# Button.net
KiCad netlist of a schematic drawn in Altium Designer
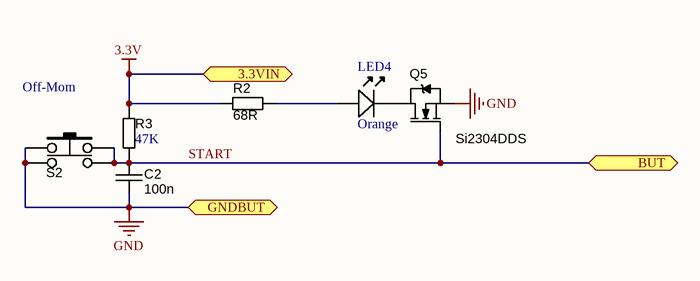
[diagram p0: Button.SchDoc]

(export (version "E")
  (design (tool "Eeschema 10.0.6"))
  (components
    (comp (ref "C2")
      (value "100n")
      (footprint "CAPC1608X90N")
      (description "Capacitor SMD Cer 100nF 10% 50V X7R 0603")
      (fields
        (field (name "TOLERANCE") "±10%")
        (field (name "MANUFACTURER") "Murata Electronics North America")
      )
      (libsource (lib "PBL - Capacitors") (part "CAPC_100n_0603_X7R_50V_10%"))
    )
    (comp (ref "LED4")
      (value "LO L296-Q2S1-24-Z")
      (footprint "LED-0603-AMBER")
      (description "LED ORANGE DIFFUSED 0603 SMD")
      (fields (field (name "COLOR") "Orange") (field (name "MANUFACTURER") "OSRAM Opto Semiconductors Inc."))
      (libsource (lib "PBL - Light Sources") (part "LED_0603_Orange"))
    )
    (comp (ref "Q5")
      (value "Si2304DDS")
      (footprint "SOT23-3")
      (description "MOSFET SMD N-CH 30V 3.6A 1.7W SOT23-3")
      (libsource (lib "PBL - Transistors") (part "MOSFET_Si2304DDS"))
    )
    (comp (ref "R2")
      (value "68R")
      (footprint "RESC1608X55N")
      (description "Resistor SMD chip 68 Ohm 0.1W 5% 0603")
      (fields (field (name "TOLERANCE") "±5%") (field (name "Comment") "Thick Film"))
      (libsource (lib "PBL - Resistors") (part "RES_68R_0603_5%"))
    )
    (comp (ref "R3")
      (value "47K")
      (footprint "RESC1608X55N")
      (description "Resistor SMD chip 47k Ohm 0.1W 1% 0603")
      (fields (field (name "TOLERANCE") "±1%") (field (name "Comment") "Thick Film"))
      (libsource (lib "PBL - Resistors") (part "RES_47K_0603_1%"))
    )
    (comp (ref "S2")
      (value "SW_NO_MOM_PVA1 OA H1 1.2N V2")
      (footprint "SW_PVA1")
      (description "Low-profile captive tact switch")
      (fields
        (field (name "MANUFACTURER") "C&K")
        (field (name "SWITCH FUNCTION") "Off-Mom")
        (field (name "MANUFACTURER PART NUMBER") "PVA1 OA H1 1.2N V2")
      )
      (libsource (lib "PBL - Switches") (part "SW_NO_MOM_PVA1OAH11.2NV2"))
    )
  )
  (nets
    (net (code "1") (name "/START") (class "Default")
      (node (ref "C2") (pin "1") (pintype "passive"))
      (node (ref "Q5") (pin "1") (pinfunction "G_1") (pintype "passive"))
      (node (ref "R3") (pin "2") (pinfunction "2_2") (pintype "passive"))
      (node (ref "S2") (pin "2") (pintype "passive"))
      (node (ref "S2") (pin "2'") (pintype "passive"))
    )
    (net (code "2") (name "3.3V") (class "Default")
      (node (ref "R2") (pin "1") (pinfunction "1_1") (pintype "passive"))
      (node (ref "R3") (pin "1") (pinfunction "1_1") (pintype "passive"))
    )
    (net (code "3") (name "GND") (class "Default")
      (node (ref "C2") (pin "2") (pintype "passive"))
      (node (ref "Q5") (pin "2") (pinfunction "S_2") (pintype "passive"))
      (node (ref "S2") (pin "1") (pintype "passive"))
      (node (ref "S2") (pin "1'") (pintype "passive"))
    )
    (net (code "4") (name "Net-(LED4-PadA)") (class "Default")
      (node (ref "LED4") (pin "A") (pinfunction "A_A") (pintype "passive"))
      (node (ref "R2") (pin "2") (pinfunction "2_2") (pintype "passive"))
    )
    (net (code "5") (name "Net-(Q5-D)") (class "Default")
      (node (ref "LED4") (pin "K") (pinfunction "K_K") (pintype "passive"))
      (node (ref "Q5") (pin "3") (pinfunction "D_3") (pintype "passive"))
    )
  )
)
